# Phone_EE445L.net
KiCad netlist of a schematic drawn in EAGLE
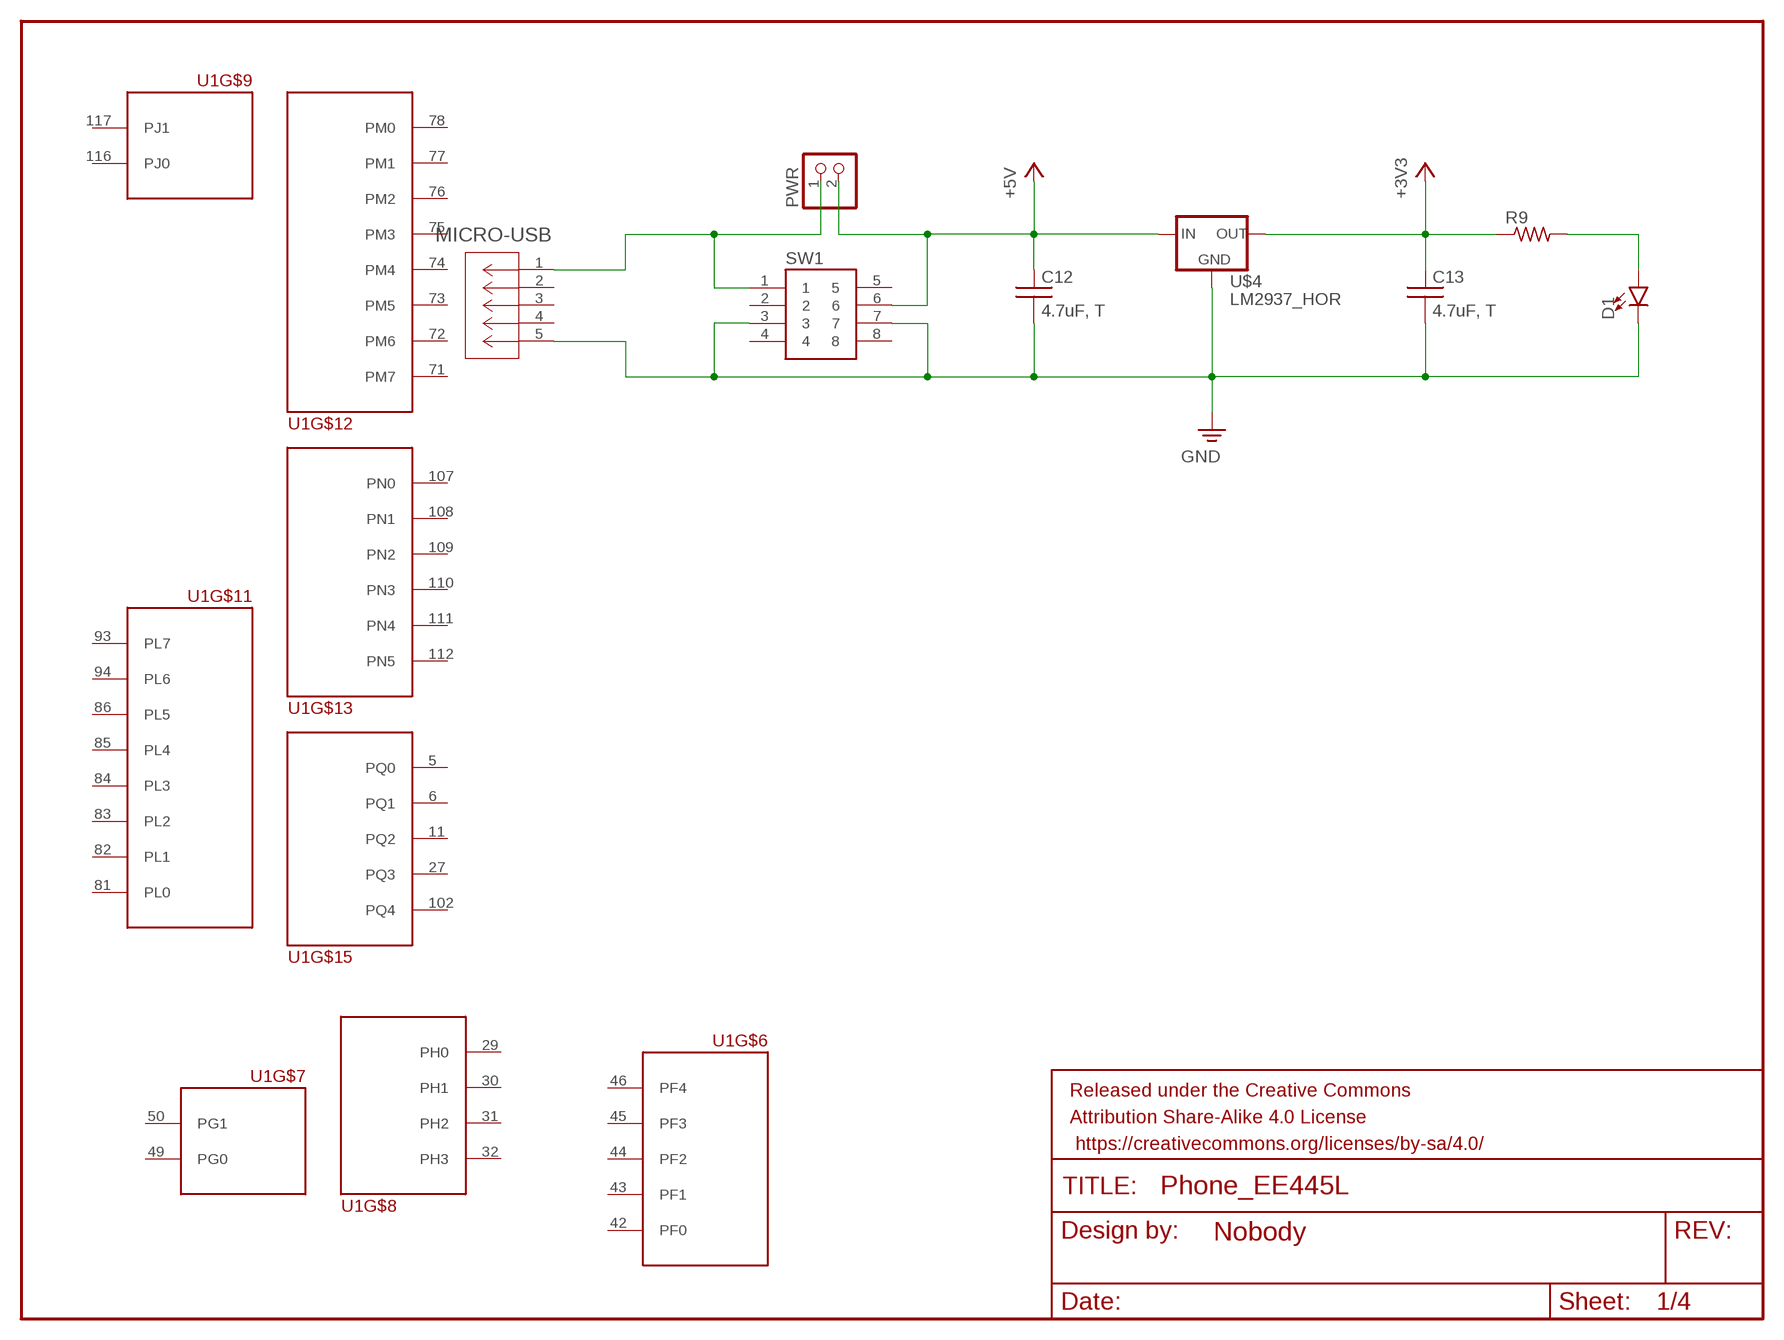
[diagram p0: schematic, sheet 1]
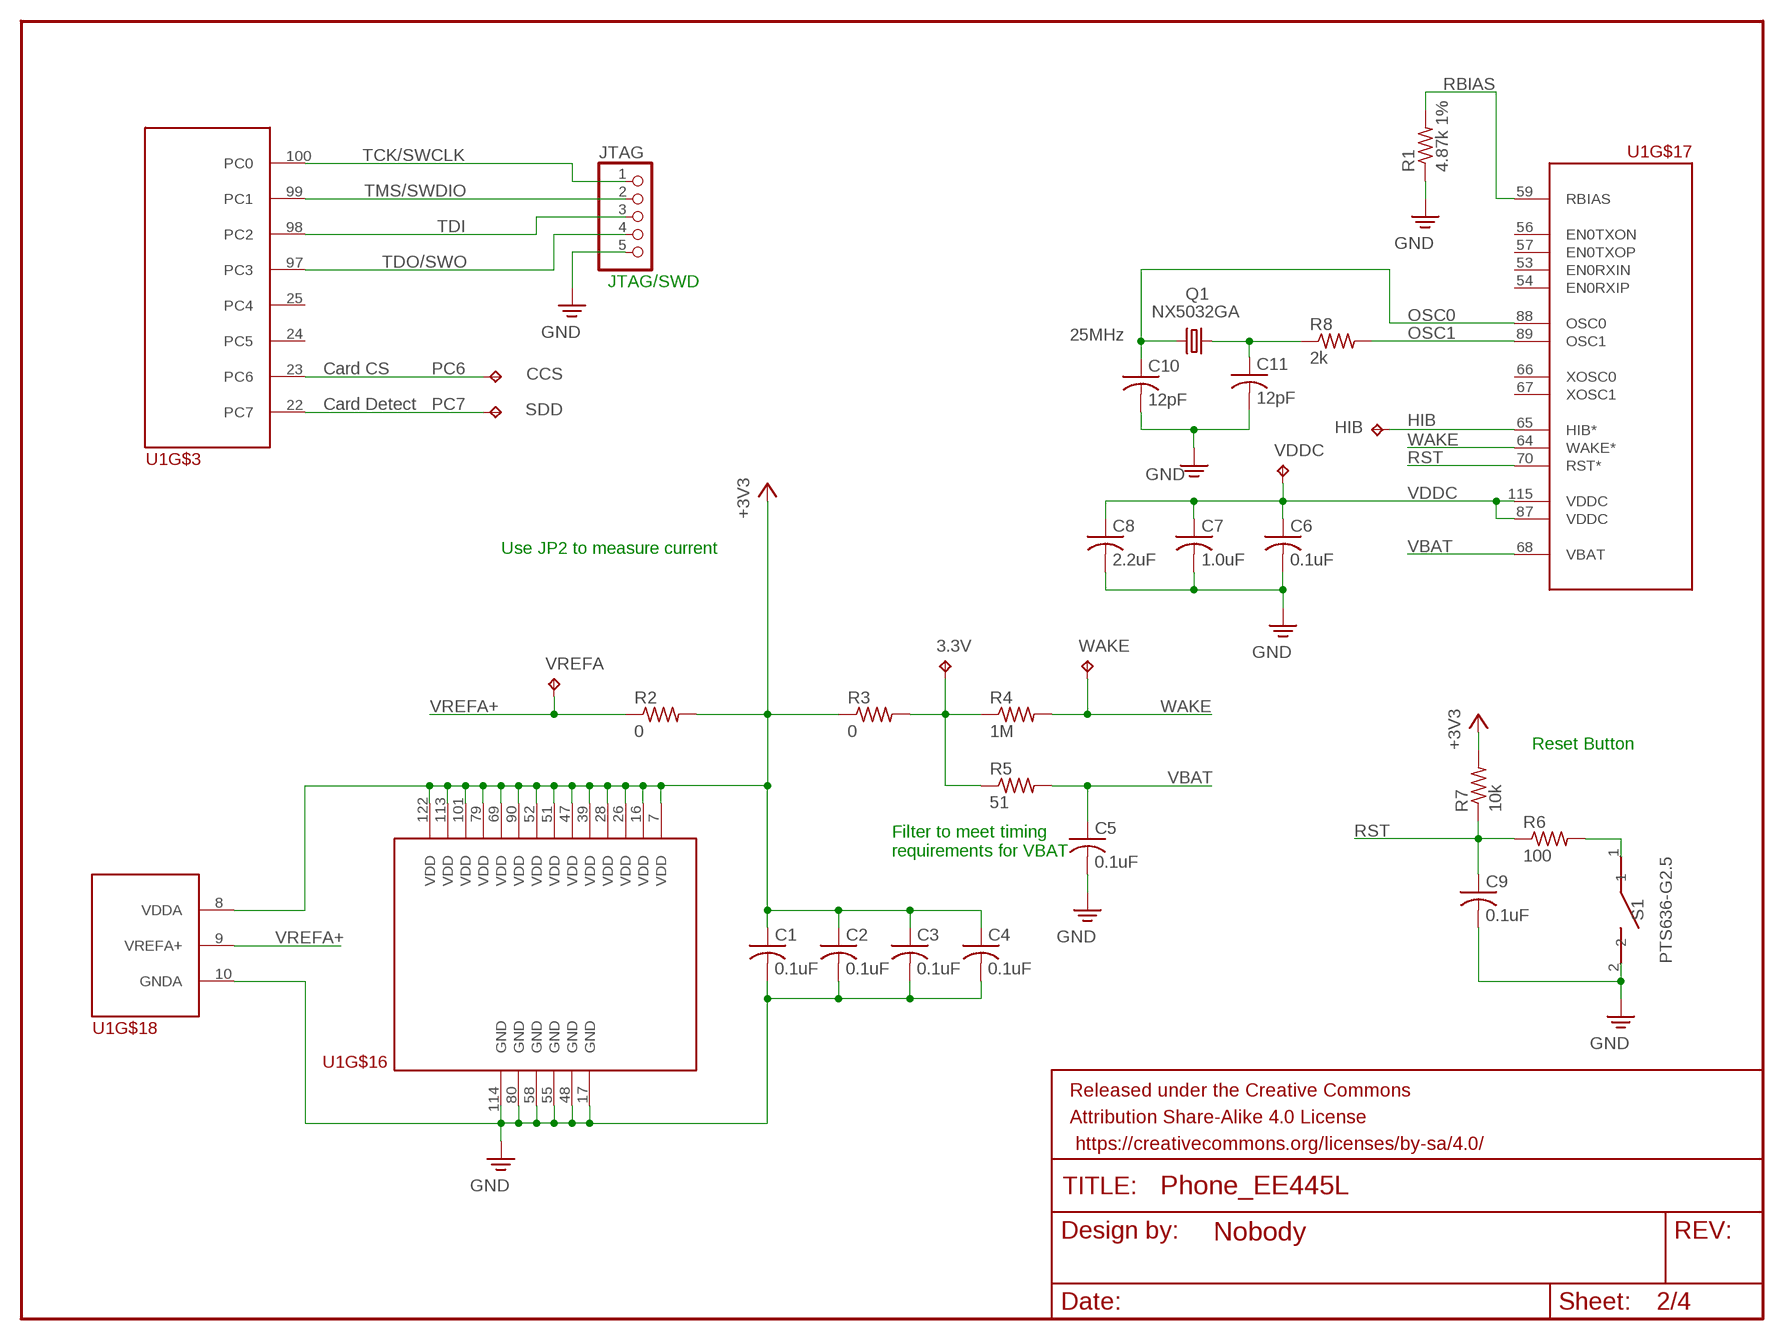
[diagram p1: schematic, sheet 2]
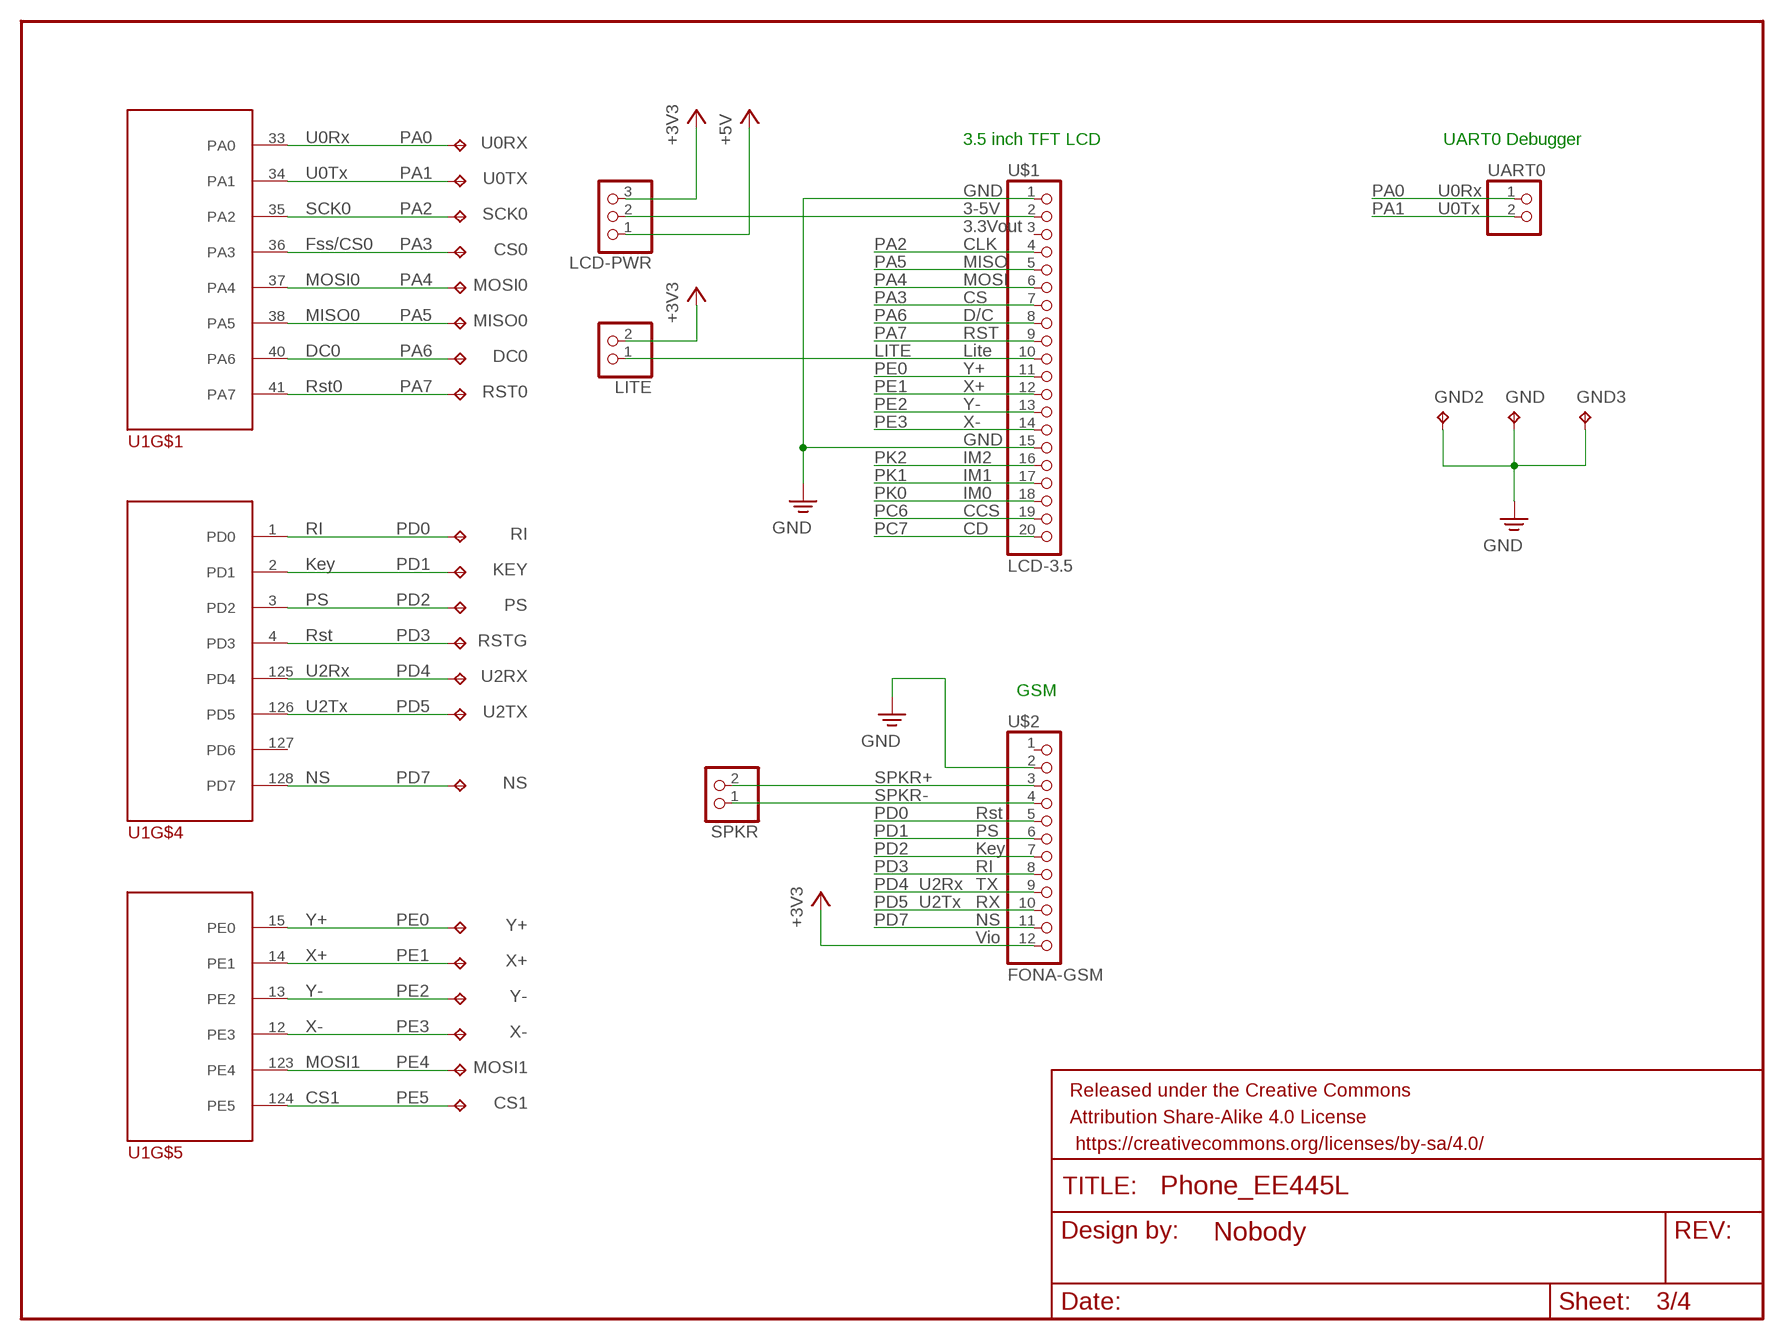
[diagram p2: schematic, sheet 3]
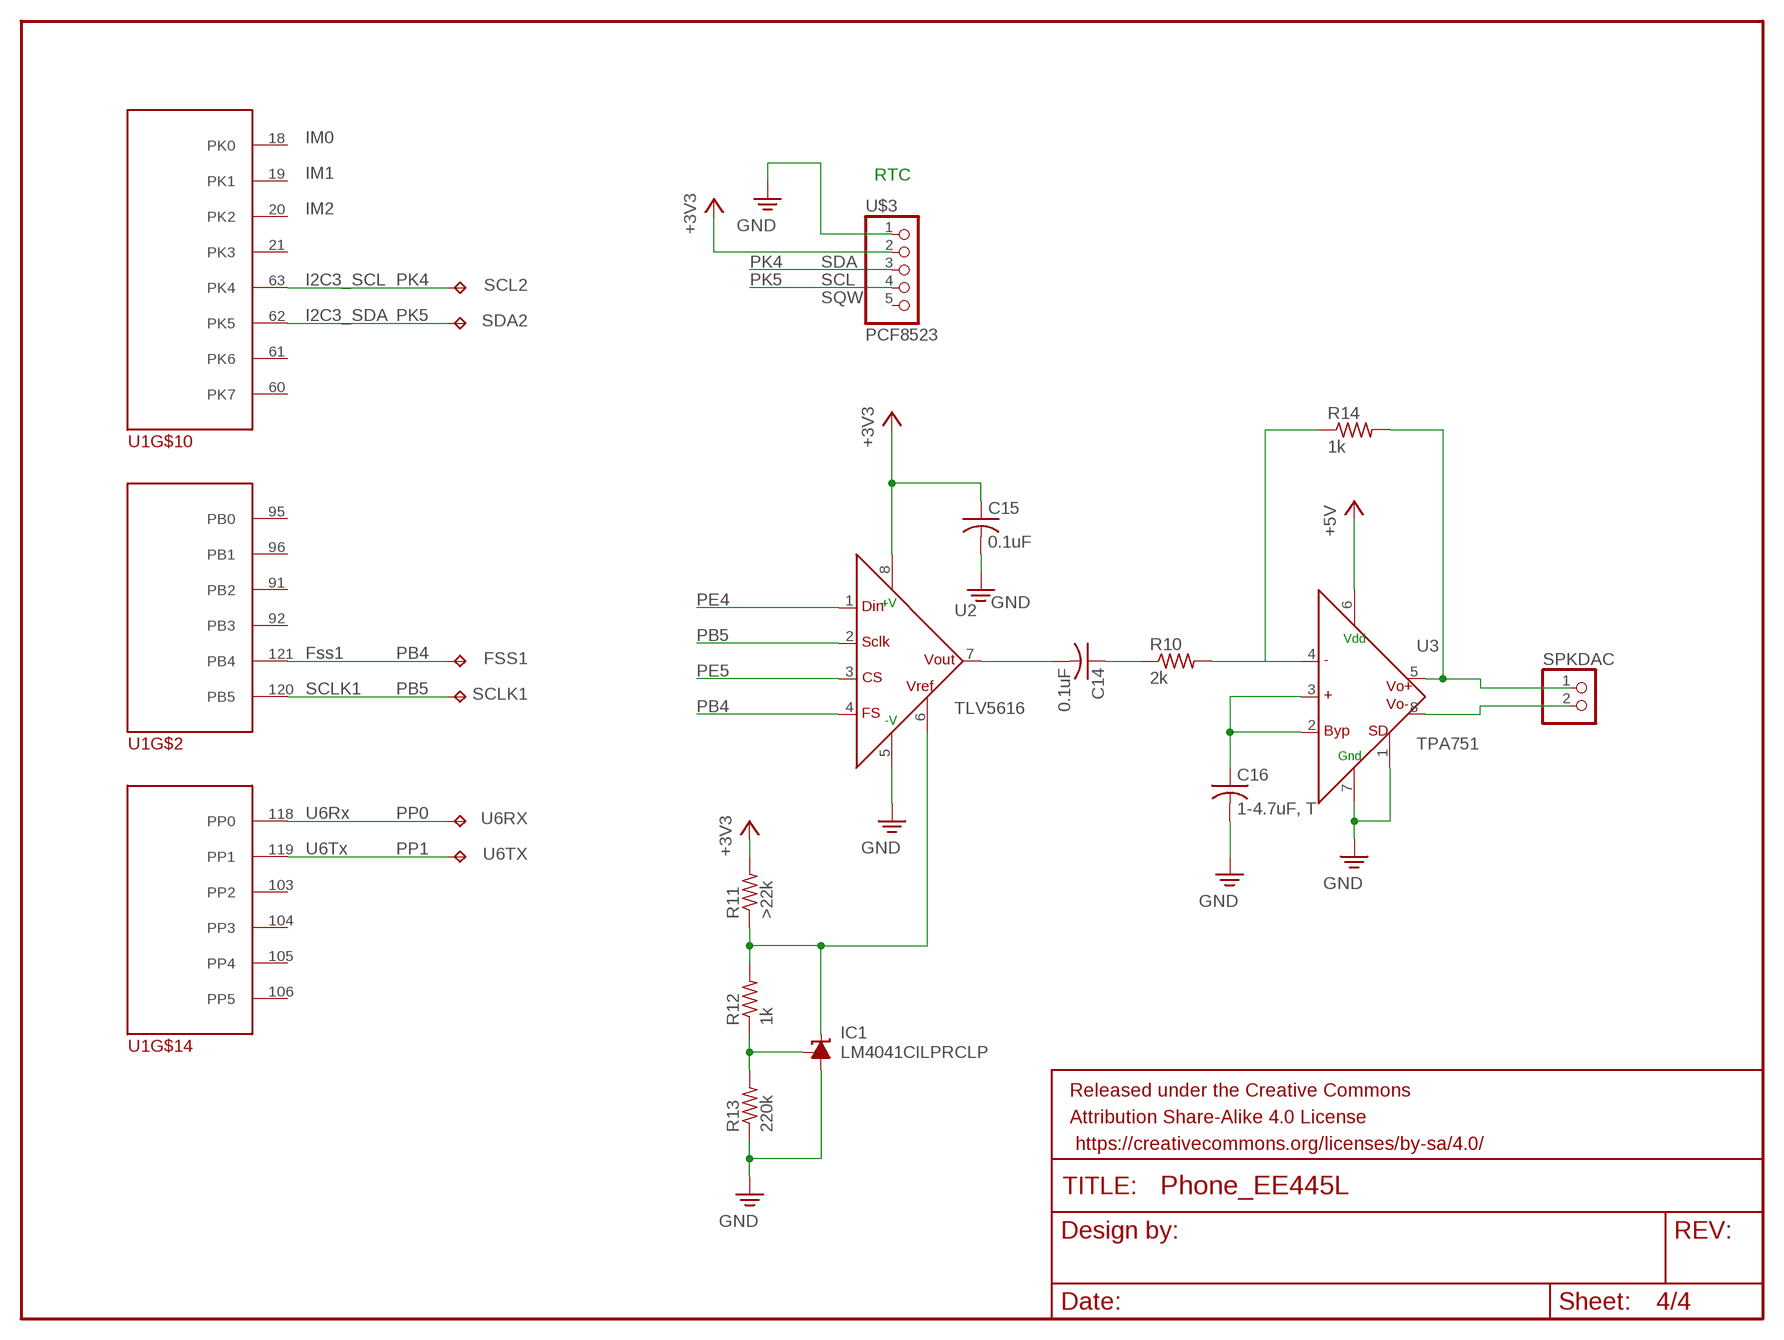
[diagram p3: schematic, sheet 4]

(export (version "E")
  (design (tool "Eeschema 10.0.6"))
  (components
    (comp (ref "C12")
      (value "4.7uF, T")
      (footprint "eagle-import:CAP200MIL")
      (libsource (lib "eagle-import") (part "CAPACITOR050-024X044"))
    )
    (comp (ref "C13")
      (value "4.7uF, T")
      (footprint "eagle-import:CAP200MIL")
      (libsource (lib "eagle-import") (part "CAPACITOR050-024X044"))
    )
    (comp (ref "D1")
      (value "LED0603")
      (footprint "eagle-import:LED-0603")
      (libsource (lib "eagle-import") (part "LED0603"))
    )
    (comp (ref "FRAME1")
      (value "FRAME-LETTERNO_PACKAGE")
      (footprint "eagle-import:DUMMY")
      (fields (field (name "DESIGNER") "Nobody"))
      (libsource (lib "eagle-import") (part "FRAME-LETTERNO_PACKAGE"))
    )
    (comp (ref "MICRO-USB")
      (value "ZX62D-B-5PA8(30)")
      (footprint "eagle-import:CONN5_ZX62D-B-5PA8")
      (fields (field (name "MANUFACTURER_PART_NUMBER") "ZX62DB5PA830"))
      (libsource (lib "eagle-import") (part "ZX62D-B-5PA8(30)"))
    )
    (comp (ref "PWR")
      (value "PINHD-1X2")
      (footprint "eagle-import:1X02")
      (libsource (lib "eagle-import") (part "PINHD-1X2"))
    )
    (comp (ref "R9")
      (value "R-US_R0805")
      (footprint "eagle-import:R0805")
      (libsource (lib "eagle-import") (part "R-US_R0805"))
    )
    (comp (ref "SW1")
      (value "PUSHBUTTON")
      (footprint "eagle-import:PWRBUTTON")
      (libsource (lib "eagle-import") (part "PUSHBUTTON"))
    )
    (comp (ref "U$4")
      (value "LM2937_HOR")
      (footprint "eagle-import:TO220")
      (libsource (lib "eagle-import") (part "LM2937_HOR"))
    )
    (comp (ref "U1")
      (value "TM4C129-MOD")
      (footprint "eagle-import:TQFP-128")
      (libsource (lib "eagle-import") (part "TM4C129-MOD"))
    )
    (comp (ref "3.3V")
      (value "TP_KEYSTONE500X")
      (footprint "eagle-import:P1.1MM")
      (libsource (lib "eagle-import") (part "TP_KEYSTONE500X"))
    )
    (comp (ref "C1")
      (value "0.1uF")
      (footprint "eagle-import:C0805")
      (libsource (lib "eagle-import") (part "C-USC0805"))
    )
    (comp (ref "C2")
      (value "0.1uF")
      (footprint "eagle-import:C0805")
      (libsource (lib "eagle-import") (part "C-USC0805"))
    )
    (comp (ref "C3")
      (value "0.1uF")
      (footprint "eagle-import:C0805")
      (libsource (lib "eagle-import") (part "C-USC0805"))
    )
    (comp (ref "C4")
      (value "0.1uF")
      (footprint "eagle-import:C0805")
      (libsource (lib "eagle-import") (part "C-USC0805"))
    )
    (comp (ref "C5")
      (value "0.1uF")
      (footprint "eagle-import:C0805")
      (libsource (lib "eagle-import") (part "C-USC0805"))
    )
    (comp (ref "C6")
      (value "0.1uF")
      (footprint "eagle-import:C0805")
      (libsource (lib "eagle-import") (part "C-USC0805"))
    )
    (comp (ref "C7")
      (value "1.0uF")
      (footprint "eagle-import:C0805")
      (libsource (lib "eagle-import") (part "C-USC0805"))
    )
    (comp (ref "C8")
      (value "2.2uF")
      (footprint "eagle-import:C0805")
      (libsource (lib "eagle-import") (part "C-USC0805"))
    )
    (comp (ref "C9")
      (value "0.1uF")
      (footprint "eagle-import:C0805")
      (libsource (lib "eagle-import") (part "C-USC0805"))
    )
    (comp (ref "C10")
      (value "12pF")
      (footprint "eagle-import:C0805")
      (libsource (lib "eagle-import") (part "C-USC0805"))
    )
    (comp (ref "C11")
      (value "12pF")
      (footprint "eagle-import:C0805")
      (libsource (lib "eagle-import") (part "C-USC0805"))
    )
    (comp (ref "CCS")
      (value "TP_KEYSTONE500X")
      (footprint "eagle-import:P1.1MM")
      (libsource (lib "eagle-import") (part "TP_KEYSTONE500X"))
    )
    (comp (ref "FRAME2")
      (value "FRAME-LETTERNO_PACKAGE")
      (footprint "eagle-import:DUMMY")
      (fields (field (name "DESIGNER") "Nobody"))
      (libsource (lib "eagle-import") (part "FRAME-LETTERNO_PACKAGE"))
    )
    (comp (ref "HIB")
      (value "TP_KEYSTONE500X")
      (footprint "eagle-import:P1.1MM")
      (libsource (lib "eagle-import") (part "TP_KEYSTONE500X"))
    )
    (comp (ref "JTAG")
      (value "PINHD-1X5")
      (footprint "eagle-import:1X05")
      (libsource (lib "eagle-import") (part "PINHD-1X5"))
    )
    (comp (ref "Q1")
      (value "NX5032GA")
      (footprint "eagle-import:NX5032GA")
      (libsource (lib "eagle-import") (part "NX5032GA"))
    )
    (comp (ref "R1")
      (value "4.87k 1%")
      (footprint "eagle-import:R0805")
      (libsource (lib "eagle-import") (part "R-US_R0805"))
    )
    (comp (ref "R2")
      (value "0")
      (footprint "eagle-import:R0805")
      (libsource (lib "eagle-import") (part "R-US_R0805"))
    )
    (comp (ref "R3")
      (value "0")
      (footprint "eagle-import:R0805")
      (libsource (lib "eagle-import") (part "R-US_R0805"))
    )
    (comp (ref "R4")
      (value "1M")
      (footprint "eagle-import:R0805")
      (libsource (lib "eagle-import") (part "R-US_R0805"))
    )
    (comp (ref "R5")
      (value "51")
      (footprint "eagle-import:R0805")
      (libsource (lib "eagle-import") (part "R-US_R0805"))
    )
    (comp (ref "R6")
      (value "100")
      (footprint "eagle-import:R0805")
      (libsource (lib "eagle-import") (part "R-US_R0805"))
    )
    (comp (ref "R7")
      (value "10k")
      (footprint "eagle-import:R0805")
      (libsource (lib "eagle-import") (part "R-US_R0805"))
    )
    (comp (ref "R8")
      (value "2k")
      (footprint "eagle-import:R0805")
      (libsource (lib "eagle-import") (part "R-US_R0805"))
    )
    (comp (ref "S1")
      (value "PTS636-G2.5")
      (footprint "eagle-import:PTS636-G")
      (libsource (lib "eagle-import") (part "PTS636-G2.5"))
    )
    (comp (ref "SDD")
      (value "TP_KEYSTONE500X")
      (footprint "eagle-import:P1.1MM")
      (libsource (lib "eagle-import") (part "TP_KEYSTONE500X"))
    )
    (comp (ref "VDDC")
      (value "TP_KEYSTONE500X")
      (footprint "eagle-import:P1.1MM")
      (libsource (lib "eagle-import") (part "TP_KEYSTONE500X"))
    )
    (comp (ref "VREFA")
      (value "TP_KEYSTONE500X")
      (footprint "eagle-import:P1.1MM")
      (libsource (lib "eagle-import") (part "TP_KEYSTONE500X"))
    )
    (comp (ref "WAKE")
      (value "TP_KEYSTONE500X")
      (footprint "eagle-import:P1.1MM")
      (libsource (lib "eagle-import") (part "TP_KEYSTONE500X"))
    )
    (comp (ref "CS0")
      (value "TP_KEYSTONE500X")
      (footprint "eagle-import:P1.1MM")
      (libsource (lib "eagle-import") (part "TP_KEYSTONE500X"))
    )
    (comp (ref "CS1")
      (value "TP_KEYSTONE500X")
      (footprint "eagle-import:P1.1MM")
      (libsource (lib "eagle-import") (part "TP_KEYSTONE500X"))
    )
    (comp (ref "DC0")
      (value "TP_KEYSTONE500X")
      (footprint "eagle-import:P1.1MM")
      (libsource (lib "eagle-import") (part "TP_KEYSTONE500X"))
    )
    (comp (ref "FRAME3")
      (value "FRAME-LETTERNO_PACKAGE")
      (footprint "eagle-import:DUMMY")
      (fields (field (name "DESIGNER") "Nobody"))
      (libsource (lib "eagle-import") (part "FRAME-LETTERNO_PACKAGE"))
    )
    (comp (ref "GND")
      (value "TP_KEYSTONE500X")
      (footprint "eagle-import:P1.1MM")
      (libsource (lib "eagle-import") (part "TP_KEYSTONE500X"))
    )
    (comp (ref "GND2")
      (value "TP_KEYSTONE500X")
      (footprint "eagle-import:P1.1MM")
      (libsource (lib "eagle-import") (part "TP_KEYSTONE500X"))
    )
    (comp (ref "GND3")
      (value "TP_KEYSTONE500X")
      (footprint "eagle-import:P1.1MM")
      (libsource (lib "eagle-import") (part "TP_KEYSTONE500X"))
    )
    (comp (ref "KEY")
      (value "TP_KEYSTONE500X")
      (footprint "eagle-import:P1.1MM")
      (libsource (lib "eagle-import") (part "TP_KEYSTONE500X"))
    )
    (comp (ref "LCD-PWR")
      (value "PINHD-1X3")
      (footprint "eagle-import:1X03")
      (libsource (lib "eagle-import") (part "PINHD-1X3"))
    )
    (comp (ref "LITE")
      (value "PINHD-1X2")
      (footprint "eagle-import:1X02")
      (libsource (lib "eagle-import") (part "PINHD-1X2"))
    )
    (comp (ref "MISO0")
      (value "TP_KEYSTONE500X")
      (footprint "eagle-import:P1.1MM")
      (libsource (lib "eagle-import") (part "TP_KEYSTONE500X"))
    )
    (comp (ref "MOSI0")
      (value "TP_KEYSTONE500X")
      (footprint "eagle-import:P1.1MM")
      (libsource (lib "eagle-import") (part "TP_KEYSTONE500X"))
    )
    (comp (ref "MOSI1")
      (value "TP_KEYSTONE500X")
      (footprint "eagle-import:P1.1MM")
      (libsource (lib "eagle-import") (part "TP_KEYSTONE500X"))
    )
    (comp (ref "NS")
      (value "TP_KEYSTONE500X")
      (footprint "eagle-import:P1.1MM")
      (libsource (lib "eagle-import") (part "TP_KEYSTONE500X"))
    )
    (comp (ref "PS")
      (value "TP_KEYSTONE500X")
      (footprint "eagle-import:P1.1MM")
      (libsource (lib "eagle-import") (part "TP_KEYSTONE500X"))
    )
    (comp (ref "RI")
      (value "TP_KEYSTONE500X")
      (footprint "eagle-import:P1.1MM")
      (libsource (lib "eagle-import") (part "TP_KEYSTONE500X"))
    )
    (comp (ref "RST0")
      (value "TP_KEYSTONE500X")
      (footprint "eagle-import:P1.1MM")
      (libsource (lib "eagle-import") (part "TP_KEYSTONE500X"))
    )
    (comp (ref "RSTG")
      (value "TP_KEYSTONE500X")
      (footprint "eagle-import:P1.1MM")
      (libsource (lib "eagle-import") (part "TP_KEYSTONE500X"))
    )
    (comp (ref "SCK0")
      (value "TP_KEYSTONE500X")
      (footprint "eagle-import:P1.1MM")
      (libsource (lib "eagle-import") (part "TP_KEYSTONE500X"))
    )
    (comp (ref "SPKR")
      (value "PINHD-1X2")
      (footprint "eagle-import:1X02")
      (libsource (lib "eagle-import") (part "PINHD-1X2"))
    )
    (comp (ref "U$1")
      (value "LCD-3.5")
      (footprint "eagle-import:LCD3.5IN")
      (libsource (lib "eagle-import") (part "LCD-3.5"))
    )
    (comp (ref "U$2")
      (value "FONA-GSM")
      (footprint "eagle-import:FONA")
      (libsource (lib "eagle-import") (part "FONA-GSM"))
    )
    (comp (ref "U0RX")
      (value "TP_KEYSTONE500X")
      (footprint "eagle-import:P1.1MM")
      (libsource (lib "eagle-import") (part "TP_KEYSTONE500X"))
    )
    (comp (ref "U0TX")
      (value "TP_KEYSTONE500X")
      (footprint "eagle-import:P1.1MM")
      (libsource (lib "eagle-import") (part "TP_KEYSTONE500X"))
    )
    (comp (ref "U2RX")
      (value "TP_KEYSTONE500X")
      (footprint "eagle-import:P1.1MM")
      (libsource (lib "eagle-import") (part "TP_KEYSTONE500X"))
    )
    (comp (ref "U2TX")
      (value "TP_KEYSTONE500X")
      (footprint "eagle-import:P1.1MM")
      (libsource (lib "eagle-import") (part "TP_KEYSTONE500X"))
    )
    (comp (ref "UART0")
      (value "PINHD-1X2")
      (footprint "eagle-import:1X02")
      (libsource (lib "eagle-import") (part "PINHD-1X2"))
    )
    (comp (ref "X+")
      (value "TP_KEYSTONE500X")
      (footprint "eagle-import:P1.1MM")
      (libsource (lib "eagle-import") (part "TP_KEYSTONE500X"))
    )
    (comp (ref "X-")
      (value "TP_KEYSTONE500X")
      (footprint "eagle-import:P1.1MM")
      (libsource (lib "eagle-import") (part "TP_KEYSTONE500X"))
    )
    (comp (ref "Y+")
      (value "TP_KEYSTONE500X")
      (footprint "eagle-import:P1.1MM")
      (libsource (lib "eagle-import") (part "TP_KEYSTONE500X"))
    )
    (comp (ref "Y-")
      (value "TP_KEYSTONE500X")
      (footprint "eagle-import:P1.1MM")
      (libsource (lib "eagle-import") (part "TP_KEYSTONE500X"))
    )
    (comp (ref "C14")
      (value "0.1uF")
      (footprint "eagle-import:C0805")
      (libsource (lib "eagle-import") (part "C-USC0805"))
    )
    (comp (ref "C15")
      (value "0.1uF")
      (footprint "eagle-import:C0805")
      (libsource (lib "eagle-import") (part "C-USC0805"))
    )
    (comp (ref "C16")
      (value "1-4.7uF, T")
      (footprint "eagle-import:C0805")
      (libsource (lib "eagle-import") (part "C-USC0805"))
    )
    (comp (ref "FRAME4")
      (value "FRAME-LETTERNO_PACKAGE")
      (footprint "eagle-import:DUMMY")
      (fields (field (name "DESIGNER") "Nobody"))
      (libsource (lib "eagle-import") (part "SparkFun-Aesthetics_507_FRAME-LETTERNO_PACKAGE"))
    )
    (comp (ref "FSS1")
      (value "TP_KEYSTONE500X")
      (footprint "eagle-import:P1.1MM")
      (libsource (lib "eagle-import") (part "TP_KEYSTONE500X"))
    )
    (comp (ref "IC1")
      (value "LM4041CILPRCLP")
      (footprint "eagle-import:LP_O-PBCY-W3")
      (fields (field (name "MPN") "LM4041CILP"))
      (libsource (lib "eagle-import") (part "LM4041CILPRLPC"))
    )
    (comp (ref "R10")
      (value "2k")
      (footprint "eagle-import:R0805")
      (libsource (lib "eagle-import") (part "R-US_R0805"))
    )
    (comp (ref "R11")
      (value ">22k")
      (footprint "eagle-import:R0805")
      (libsource (lib "eagle-import") (part "R-US_R0805"))
    )
    (comp (ref "R12")
      (value "1k")
      (footprint "eagle-import:R0805")
      (libsource (lib "eagle-import") (part "R-US_R0805"))
    )
    (comp (ref "R13")
      (value "220k")
      (footprint "eagle-import:R0805")
      (libsource (lib "eagle-import") (part "R-US_R0805"))
    )
    (comp (ref "R14")
      (value "1k")
      (footprint "eagle-import:R0805")
      (libsource (lib "eagle-import") (part "R-US_R0805"))
    )
    (comp (ref "SCL2")
      (value "TP_KEYSTONE500X")
      (footprint "eagle-import:P1.1MM")
      (libsource (lib "eagle-import") (part "TP_KEYSTONE500X"))
    )
    (comp (ref "SCLK1")
      (value "TP_KEYSTONE500X")
      (footprint "eagle-import:P1.1MM")
      (libsource (lib "eagle-import") (part "TP_KEYSTONE500X"))
    )
    (comp (ref "SDA2")
      (value "TP_KEYSTONE500X")
      (footprint "eagle-import:P1.1MM")
      (libsource (lib "eagle-import") (part "TP_KEYSTONE500X"))
    )
    (comp (ref "SPKDAC")
      (value "PINHD-1X2")
      (footprint "eagle-import:1X02")
      (libsource (lib "eagle-import") (part "PINHD-1X2"))
    )
    (comp (ref "U$3")
      (value "PCF8523")
      (footprint "eagle-import:PCF8523")
      (libsource (lib "eagle-import") (part "PCF8523"))
    )
    (comp (ref "U2")
      (value "TLV5616")
      (footprint "eagle-import:DIL08")
      (libsource (lib "eagle-import") (part "TLV5616"))
    )
    (comp (ref "U3")
      (value "TPA751")
      (footprint "eagle-import:SO08")
      (libsource (lib "eagle-import") (part "TPA751"))
    )
    (comp (ref "U6RX")
      (value "TP_KEYSTONE500X")
      (footprint "eagle-import:P1.1MM")
      (libsource (lib "eagle-import") (part "TP_KEYSTONE500X"))
    )
    (comp (ref "U6TX")
      (value "TP_KEYSTONE500X")
      (footprint "eagle-import:P1.1MM")
      (libsource (lib "eagle-import") (part "TP_KEYSTONE500X"))
    )
  )
  (nets
    (net (code "1") (name "+3V3") (class "Default")
      (node (ref "C1") (pin "1") (pinfunction "1_1") (pintype "passive"))
      (node (ref "C13") (pin "1") (pinfunction "1_1") (pintype "passive"))
      (node (ref "C15") (pin "1") (pinfunction "1_1") (pintype "passive"))
      (node (ref "C2") (pin "1") (pinfunction "1_1") (pintype "passive"))
      (node (ref "C3") (pin "1") (pinfunction "1_1") (pintype "passive"))
      (node (ref "C4") (pin "1") (pinfunction "1_1") (pintype "passive"))
      (node (ref "LCD-PWR") (pin "3") (pinfunction "3_3") (pintype "passive"))
      (node (ref "LITE") (pin "2") (pinfunction "2_2") (pintype "passive"))
      (node (ref "R11") (pin "2") (pinfunction "2_2") (pintype "passive"))
      (node (ref "R2") (pin "2") (pinfunction "2_2") (pintype "passive"))
      (node (ref "R3") (pin "1") (pinfunction "1_1") (pintype "passive"))
      (node (ref "R7") (pin "2") (pinfunction "2_2") (pintype "passive"))
      (node (ref "R9") (pin "1") (pinfunction "1_1") (pintype "passive"))
      (node (ref "U$2") (pin "12") (pinfunction "12_12") (pintype "passive"))
      (node (ref "U$3") (pin "2") (pinfunction "2_2") (pintype "passive"))
      (node (ref "U$4") (pin "3") (pinfunction "OUT_3") (pintype "passive"))
      (node (ref "U1") (pin "101") (pinfunction "VDD_101") (pintype "power_in"))
      (node (ref "U1") (pin "113") (pinfunction "VDD_113") (pintype "power_in"))
      (node (ref "U1") (pin "122") (pinfunction "VDD_122") (pintype "power_in"))
      (node (ref "U1") (pin "16") (pinfunction "VDD_16") (pintype "power_in"))
      (node (ref "U1") (pin "26") (pinfunction "VDD_26") (pintype "power_in"))
      (node (ref "U1") (pin "28") (pinfunction "VDD_28") (pintype "power_in"))
      (node (ref "U1") (pin "39") (pinfunction "VDD_39") (pintype "power_in"))
      (node (ref "U1") (pin "47") (pinfunction "VDD_47") (pintype "power_in"))
      (node (ref "U1") (pin "51") (pinfunction "VDD_51") (pintype "power_in"))
      (node (ref "U1") (pin "52") (pinfunction "VDD_52") (pintype "power_in"))
      (node (ref "U1") (pin "69") (pinfunction "VDD_69") (pintype "power_in"))
      (node (ref "U1") (pin "7") (pinfunction "VDD_7") (pintype "power_in"))
      (node (ref "U1") (pin "79") (pinfunction "VDD_79") (pintype "power_in"))
      (node (ref "U1") (pin "8") (pinfunction "VDDA_8") (pintype "power_in"))
      (node (ref "U1") (pin "90") (pinfunction "VDD_90") (pintype "power_in"))
      (node (ref "U2") (pin "8") (pinfunction "VDD_8") (pintype "power_in"))
    )
    (net (code "2") (name "+5V") (class "Default")
      (node (ref "C12") (pin "1") (pinfunction "1_1") (pintype "passive"))
      (node (ref "LCD-PWR") (pin "1") (pinfunction "1_1") (pintype "passive"))
      (node (ref "PWR") (pin "2") (pinfunction "2_2") (pintype "passive"))
      (node (ref "SW1") (pin "6") (pinfunction "6_6") (pintype "output"))
      (node (ref "U$4") (pin "1") (pinfunction "IN_1") (pintype "input"))
      (node (ref "U3") (pin "6") (pinfunction "VDD_6") (pintype "power_in"))
    )
    (net (code "3") (name "GND") (class "Default")
      (node (ref "C1") (pin "2") (pinfunction "2_2") (pintype "passive"))
      (node (ref "C10") (pin "2") (pinfunction "2_2") (pintype "passive"))
      (node (ref "C11") (pin "2") (pinfunction "2_2") (pintype "passive"))
      (node (ref "C12") (pin "2") (pinfunction "2_2") (pintype "passive"))
      (node (ref "C13") (pin "2") (pinfunction "2_2") (pintype "passive"))
      (node (ref "C15") (pin "2") (pinfunction "2_2") (pintype "passive"))
      (node (ref "C16") (pin "2") (pinfunction "2_2") (pintype "passive"))
      (node (ref "C2") (pin "2") (pinfunction "2_2") (pintype "passive"))
      (node (ref "C3") (pin "2") (pinfunction "2_2") (pintype "passive"))
      (node (ref "C4") (pin "2") (pinfunction "2_2") (pintype "passive"))
      (node (ref "C5") (pin "2") (pinfunction "2_2") (pintype "passive"))
      (node (ref "C6") (pin "2") (pinfunction "2_2") (pintype "passive"))
      (node (ref "C7") (pin "2") (pinfunction "2_2") (pintype "passive"))
      (node (ref "C8") (pin "2") (pinfunction "2_2") (pintype "passive"))
      (node (ref "C9") (pin "2") (pinfunction "2_2") (pintype "passive"))
      (node (ref "D1") (pin "C") (pinfunction "C_C") (pintype "passive"))
      (node (ref "GND") (pin "TP") (pinfunction "TP_TP") (pintype "input"))
      (node (ref "GND2") (pin "TP") (pinfunction "TP_TP") (pintype "input"))
      (node (ref "GND3") (pin "TP") (pinfunction "TP_TP") (pintype "input"))
      (node (ref "IC1") (pin "3") (pinfunction "A_3") (pintype "passive"))
      (node (ref "JTAG") (pin "5") (pinfunction "5_5") (pintype "passive"))
      (node (ref "MICRO-USB") (pin "5") (pinfunction "5_5") (pintype "passive"))
      (node (ref "R1") (pin "1") (pinfunction "1_1") (pintype "passive"))
      (node (ref "R13") (pin "1") (pinfunction "1_1") (pintype "passive"))
      (node (ref "S1") (pin "2") (pinfunction "2_2") (pintype "bidirectional"))
      (node (ref "SW1") (pin "3") (pinfunction "3_3") (pintype "power_in"))
      (node (ref "SW1") (pin "7") (pinfunction "7_7") (pintype "power_in"))
      (node (ref "U$1") (pin "1") (pinfunction "1_1") (pintype "passive"))
      (node (ref "U$1") (pin "15") (pinfunction "15_15") (pintype "passive"))
      (node (ref "U$2") (pin "2") (pinfunction "2_2") (pintype "passive"))
      (node (ref "U$3") (pin "1") (pinfunction "1_1") (pintype "passive"))
      (node (ref "U$4") (pin "2") (pinfunction "GND_2") (pintype "input"))
      (node (ref "U1") (pin "10") (pinfunction "GNDA_10") (pintype "power_in"))
      (node (ref "U1") (pin "114") (pinfunction "GND_114") (pintype "power_in"))
      (node (ref "U1") (pin "17") (pinfunction "GND_17") (pintype "power_in"))
      (node (ref "U1") (pin "48") (pinfunction "GND_48") (pintype "power_in"))
      (node (ref "U1") (pin "55") (pinfunction "GND_55") (pintype "power_in"))
      (node (ref "U1") (pin "58") (pinfunction "GND_58") (pintype "power_in"))
      (node (ref "U1") (pin "80") (pinfunction "GND_80") (pintype "power_in"))
      (node (ref "U2") (pin "5") (pinfunction "AGND_5") (pintype "power_in"))
      (node (ref "U3") (pin "1") (pinfunction "SHUTDOWN_1") (pintype "passive"))
      (node (ref "U3") (pin "7") (pinfunction "GND_7") (pintype "power_in"))
    )
    (net (code "4") (name "HIB") (class "Default")
      (node (ref "HIB") (pin "TP") (pinfunction "TP_TP") (pintype "input"))
      (node (ref "U1") (pin "65") (pinfunction "HIB*_65") (pintype "input"))
    )
    (net (code "5") (name "LITE") (class "Default")
      (node (ref "LITE") (pin "1") (pinfunction "1_1") (pintype "passive"))
      (node (ref "U$1") (pin "10") (pinfunction "10_10") (pintype "passive"))
    )
    (net (code "6") (name "Net-(3.3V-PadTP)") (class "Default")
      (node (ref "3.3V") (pin "TP") (pinfunction "TP_TP") (pintype "input"))
      (node (ref "R3") (pin "2") (pinfunction "2_2") (pintype "passive"))
      (node (ref "R4") (pin "1") (pinfunction "1_1") (pintype "passive"))
      (node (ref "R5") (pin "1") (pinfunction "1_1") (pintype "passive"))
    )
    (net (code "7") (name "Net-(C11-Pad1)") (class "Default")
      (node (ref "C11") (pin "1") (pinfunction "1_1") (pintype "passive"))
      (node (ref "Q1") (pin "1") (pinfunction "1_1") (pintype "passive"))
      (node (ref "R8") (pin "1") (pinfunction "1_1") (pintype "passive"))
    )
    (net (code "8") (name "Net-(C14-Pad1)") (class "Default")
      (node (ref "C14") (pin "1") (pinfunction "1_1") (pintype "passive"))
      (node (ref "R10") (pin "1") (pinfunction "1_1") (pintype "passive"))
    )
    (net (code "9") (name "Net-(D1-PadA)") (class "Default")
      (node (ref "D1") (pin "A") (pinfunction "A_A") (pintype "passive"))
      (node (ref "R9") (pin "2") (pinfunction "2_2") (pintype "passive"))
    )
    (net (code "10") (name "Net-(IC1-C)") (class "Default")
      (node (ref "IC1") (pin "2") (pinfunction "C_2") (pintype "passive"))
      (node (ref "R11") (pin "1") (pinfunction "1_1") (pintype "passive"))
      (node (ref "R12") (pin "2") (pinfunction "2_2") (pintype "passive"))
      (node (ref "U2") (pin "6") (pinfunction "REFIN_6") (pintype "passive"))
    )
    (net (code "11") (name "Net-(IC1-FB)") (class "Default")
      (node (ref "IC1") (pin "1") (pinfunction "FB_1") (pintype "passive"))
      (node (ref "R12") (pin "1") (pinfunction "1_1") (pintype "passive"))
      (node (ref "R13") (pin "2") (pinfunction "2_2") (pintype "passive"))
    )
    (net (code "12") (name "Net-(LCD-PWR-Pad2)") (class "Default")
      (node (ref "LCD-PWR") (pin "2") (pinfunction "2_2") (pintype "passive"))
      (node (ref "U$1") (pin "2") (pinfunction "2_2") (pintype "passive"))
    )
    (net (code "13") (name "Net-(MICRO-USB-Pad1)") (class "Default")
      (node (ref "MICRO-USB") (pin "1") (pinfunction "1_1") (pintype "passive"))
      (node (ref "PWR") (pin "1") (pinfunction "1_1") (pintype "passive"))
      (node (ref "SW1") (pin "1") (pinfunction "1_1") (pintype "input"))
    )
    (net (code "14") (name "Net-(R6-Pad2)") (class "Default")
      (node (ref "R6") (pin "2") (pinfunction "2_2") (pintype "passive"))
      (node (ref "S1") (pin "1") (pinfunction "1_1") (pintype "bidirectional"))
    )
    (net (code "15") (name "Net-(U2-OUT)") (class "Default")
      (node (ref "C14") (pin "2") (pinfunction "2_2") (pintype "passive"))
      (node (ref "U2") (pin "7") (pinfunction "OUT_7") (pintype "output"))
    )
    (net (code "16") (name "Net-(U3-BYPASS)") (class "Default")
      (node (ref "C16") (pin "1") (pinfunction "1_1") (pintype "passive"))
      (node (ref "U3") (pin "2") (pinfunction "BYPASS_2") (pintype "input"))
      (node (ref "U3") (pin "3") (pinfunction "IN+_3") (pintype "passive"))
    )
    (net (code "17") (name "Net-(U3-IN-)") (class "Default")
      (node (ref "R10") (pin "2") (pinfunction "2_2") (pintype "passive"))
      (node (ref "R14") (pin "1") (pinfunction "1_1") (pintype "passive"))
      (node (ref "U3") (pin "4") (pinfunction "IN-_4") (pintype "passive"))
    )
    (net (code "18") (name "Net-(U3-VO+)") (class "Default")
      (node (ref "R14") (pin "2") (pinfunction "2_2") (pintype "passive"))
      (node (ref "SPKDAC") (pin "1") (pinfunction "1_1") (pintype "passive"))
      (node (ref "U3") (pin "5") (pinfunction "VO+_5") (pintype "output"))
    )
    (net (code "19") (name "Net-(U3-VO-)") (class "Default")
      (node (ref "SPKDAC") (pin "2") (pinfunction "2_2") (pintype "passive"))
      (node (ref "U3") (pin "8") (pinfunction "VO-_8") (pintype "output"))
    )
    (net (code "20") (name "OSC0") (class "Default")
      (node (ref "C10") (pin "1") (pinfunction "1_1") (pintype "passive"))
      (node (ref "Q1") (pin "2") (pinfunction "2_2") (pintype "passive"))
      (node (ref "U1") (pin "88") (pinfunction "OSC0_88") (pintype "bidirectional"))
    )
    (net (code "21") (name "OSC1") (class "Default")
      (node (ref "R8") (pin "2") (pinfunction "2_2") (pintype "passive"))
      (node (ref "U1") (pin "89") (pinfunction "OSC1_89") (pintype "bidirectional"))
    )
    (net (code "22") (name "PA0") (class "Default")
      (node (ref "U0RX") (pin "TP") (pinfunction "TP_TP") (pintype "input"))
      (node (ref "U1") (pin "33") (pinfunction "PA0_33") (pintype "bidirectional"))
      (node (ref "UART0") (pin "1") (pinfunction "1_1") (pintype "passive"))
    )
    (net (code "23") (name "PA1") (class "Default")
      (node (ref "U0TX") (pin "TP") (pinfunction "TP_TP") (pintype "input"))
      (node (ref "U1") (pin "34") (pinfunction "PA1_34") (pintype "bidirectional"))
      (node (ref "UART0") (pin "2") (pinfunction "2_2") (pintype "passive"))
    )
    (net (code "24") (name "PA2") (class "Default")
      (node (ref "SCK0") (pin "TP") (pinfunction "TP_TP") (pintype "input"))
      (node (ref "U$1") (pin "4") (pinfunction "4_4") (pintype "passive"))
      (node (ref "U1") (pin "35") (pinfunction "PA2_35") (pintype "bidirectional"))
    )
    (net (code "25") (name "PA3") (class "Default")
      (node (ref "CS0") (pin "TP") (pinfunction "TP_TP") (pintype "input"))
      (node (ref "U$1") (pin "7") (pinfunction "7_7") (pintype "passive"))
      (node (ref "U1") (pin "36") (pinfunction "PA3_36") (pintype "bidirectional"))
    )
    (net (code "26") (name "PA4") (class "Default")
      (node (ref "MOSI0") (pin "TP") (pinfunction "TP_TP") (pintype "input"))
      (node (ref "U$1") (pin "6") (pinfunction "6_6") (pintype "passive"))
      (node (ref "U1") (pin "37") (pinfunction "PA4_37") (pintype "bidirectional"))
    )
    (net (code "27") (name "PA5") (class "Default")
      (node (ref "MISO0") (pin "TP") (pinfunction "TP_TP") (pintype "input"))
      (node (ref "U$1") (pin "5") (pinfunction "5_5") (pintype "passive"))
      (node (ref "U1") (pin "38") (pinfunction "PA5_38") (pintype "bidirectional"))
    )
    (net (code "28") (name "PA6") (class "Default")
      (node (ref "DC0") (pin "TP") (pinfunction "TP_TP") (pintype "input"))
      (node (ref "U$1") (pin "8") (pinfunction "8_8") (pintype "passive"))
      (node (ref "U1") (pin "40") (pinfunction "PA6_40") (pintype "bidirectional"))
    )
    (net (code "29") (name "PA7") (class "Default")
      (node (ref "RST0") (pin "TP") (pinfunction "TP_TP") (pintype "input"))
      (node (ref "U$1") (pin "9") (pinfunction "9_9") (pintype "passive"))
      (node (ref "U1") (pin "41") (pinfunction "PA7_41") (pintype "bidirectional"))
    )
    (net (code "30") (name "PB4") (class "Default")
      (node (ref "FSS1") (pin "TP") (pinfunction "TP_TP") (pintype "input"))
      (node (ref "U1") (pin "121") (pinfunction "PB4_121") (pintype "bidirectional"))
      (node (ref "U2") (pin "4") (pinfunction "FS_4") (pintype "input"))
    )
    (net (code "31") (name "PB5") (class "Default")
      (node (ref "SCLK1") (pin "TP") (pinfunction "TP_TP") (pintype "input"))
      (node (ref "U1") (pin "120") (pinfunction "PB5_120") (pintype "bidirectional"))
      (node (ref "U2") (pin "2") (pinfunction "SCLK_2") (pintype "input"))
    )
    (net (code "32") (name "PC6") (class "Default")
      (node (ref "CCS") (pin "TP") (pinfunction "TP_TP") (pintype "input"))
      (node (ref "U$1") (pin "19") (pinfunction "19_19") (pintype "passive"))
      (node (ref "U1") (pin "23") (pinfunction "PC6_23") (pintype "bidirectional"))
    )
    (net (code "33") (name "PC7") (class "Default")
      (node (ref "SDD") (pin "TP") (pinfunction "TP_TP") (pintype "input"))
      (node (ref "U$1") (pin "20") (pinfunction "20_20") (pintype "passive"))
      (node (ref "U1") (pin "22") (pinfunction "PC7_22") (pintype "bidirectional"))
    )
    (net (code "34") (name "PD0") (class "Default")
      (node (ref "RI") (pin "TP") (pinfunction "TP_TP") (pintype "input"))
      (node (ref "U$2") (pin "5") (pinfunction "5_5") (pintype "passive"))
      (node (ref "U1") (pin "1") (pinfunction "PD0_1") (pintype "bidirectional"))
    )
    (net (code "35") (name "PD1") (class "Default")
      (node (ref "KEY") (pin "TP") (pinfunction "TP_TP") (pintype "input"))
      (node (ref "U$2") (pin "6") (pinfunction "6_6") (pintype "passive"))
      (node (ref "U1") (pin "2") (pinfunction "PD1_2") (pintype "bidirectional"))
    )
    (net (code "36") (name "PD2") (class "Default")
      (node (ref "PS") (pin "TP") (pinfunction "TP_TP") (pintype "input"))
      (node (ref "U$2") (pin "7") (pinfunction "7_7") (pintype "passive"))
      (node (ref "U1") (pin "3") (pinfunction "PD2_3") (pintype "bidirectional"))
    )
    (net (code "37") (name "PD3") (class "Default")
      (node (ref "RSTG") (pin "TP") (pinfunction "TP_TP") (pintype "input"))
      (node (ref "U$2") (pin "8") (pinfunction "8_8") (pintype "passive"))
      (node (ref "U1") (pin "4") (pinfunction "PD3_4") (pintype "bidirectional"))
    )
    (net (code "38") (name "PD4") (class "Default")
      (node (ref "U$2") (pin "9") (pinfunction "9_9") (pintype "passive"))
      (node (ref "U1") (pin "125") (pinfunction "PD4_125") (pintype "bidirectional"))
      (node (ref "U2RX") (pin "TP") (pinfunction "TP_TP") (pintype "input"))
    )
    (net (code "39") (name "PD5") (class "Default")
      (node (ref "U$2") (pin "10") (pinfunction "10_10") (pintype "passive"))
      (node (ref "U1") (pin "126") (pinfunction "PD5_126") (pintype "bidirectional"))
      (node (ref "U2TX") (pin "TP") (pinfunction "TP_TP") (pintype "input"))
    )
    (net (code "40") (name "PD7") (class "Default")
      (node (ref "NS") (pin "TP") (pinfunction "TP_TP") (pintype "input"))
      (node (ref "U$2") (pin "11") (pinfunction "11_11") (pintype "passive"))
      (node (ref "U1") (pin "128") (pinfunction "PD7_128") (pintype "bidirectional"))
    )
    (net (code "41") (name "PE0") (class "Default")
      (node (ref "U$1") (pin "11") (pinfunction "11_11") (pintype "passive"))
      (node (ref "U1") (pin "15") (pinfunction "PE0_15") (pintype "bidirectional"))
      (node (ref "Y+") (pin "TP") (pinfunction "TP_TP") (pintype "input"))
    )
    (net (code "42") (name "PE1") (class "Default")
      (node (ref "U$1") (pin "12") (pinfunction "12_12") (pintype "passive"))
      (node (ref "U1") (pin "14") (pinfunction "PE1_14") (pintype "bidirectional"))
      (node (ref "X+") (pin "TP") (pinfunction "TP_TP") (pintype "input"))
    )
    (net (code "43") (name "PE2") (class "Default")
      (node (ref "U$1") (pin "13") (pinfunction "13_13") (pintype "passive"))
      (node (ref "U1") (pin "13") (pinfunction "PE2_13") (pintype "bidirectional"))
      (node (ref "Y-") (pin "TP") (pinfunction "TP_TP") (pintype "input"))
    )
    (net (code "44") (name "PE3") (class "Default")
      (node (ref "U$1") (pin "14") (pinfunction "14_14") (pintype "passive"))
      (node (ref "U1") (pin "12") (pinfunction "PE3_12") (pintype "bidirectional"))
      (node (ref "X-") (pin "TP") (pinfunction "TP_TP") (pintype "input"))
    )
    (net (code "45") (name "PE4") (class "Default")
      (node (ref "MOSI1") (pin "TP") (pinfunction "TP_TP") (pintype "input"))
      (node (ref "U1") (pin "123") (pinfunction "PE4_123") (pintype "bidirectional"))
      (node (ref "U2") (pin "1") (pinfunction "DIN_1") (pintype "input"))
    )
    (net (code "46") (name "PE5") (class "Default")
      (node (ref "CS1") (pin "TP") (pinfunction "TP_TP") (pintype "input"))
      (node (ref "U1") (pin "124") (pinfunction "PE5_124") (pintype "bidirectional"))
      (node (ref "U2") (pin "3") (pinfunction "CS_3") (pintype "input"))
    )
    (net (code "47") (name "PK0") (class "Default")
      (node (ref "U$1") (pin "18") (pinfunction "18_18") (pintype "passive"))
    )
    (net (code "48") (name "PK1") (class "Default")
      (node (ref "U$1") (pin "17") (pinfunction "17_17") (pintype "passive"))
    )
    (net (code "49") (name "PK2") (class "Default")
      (node (ref "U$1") (pin "16") (pinfunction "16_16") (pintype "passive"))
    )
    (net (code "50") (name "PK4") (class "Default")
      (node (ref "SCL2") (pin "TP") (pinfunction "TP_TP") (pintype "input"))
      (node (ref "U$3") (pin "3") (pinfunction "3_3") (pintype "passive"))
      (node (ref "U1") (pin "63") (pinfunction "PK4_63") (pintype "bidirectional"))
    )
    (net (code "51") (name "PK5") (class "Default")
      (node (ref "SDA2") (pin "TP") (pinfunction "TP_TP") (pintype "input"))
      (node (ref "U$3") (pin "4") (pinfunction "4_4") (pintype "passive"))
      (node (ref "U1") (pin "62") (pinfunction "PK5_62") (pintype "bidirectional"))
    )
    (net (code "52") (name "PP0") (class "Default")
      (node (ref "U1") (pin "118") (pinfunction "PP0_118") (pintype "bidirectional"))
      (node (ref "U6RX") (pin "TP") (pinfunction "TP_TP") (pintype "input"))
    )
    (net (code "53") (name "PP1") (class "Default")
      (node (ref "U1") (pin "119") (pinfunction "PP1_119") (pintype "bidirectional"))
      (node (ref "U6TX") (pin "TP") (pinfunction "TP_TP") (pintype "input"))
    )
    (net (code "54") (name "RBIAS") (class "Default")
      (node (ref "R1") (pin "2") (pinfunction "2_2") (pintype "passive"))
      (node (ref "U1") (pin "59") (pinfunction "RBIAS_59") (pintype "bidirectional"))
    )
    (net (code "55") (name "RST") (class "Default")
      (node (ref "C9") (pin "1") (pinfunction "1_1") (pintype "passive"))
      (node (ref "R6") (pin "1") (pinfunction "1_1") (pintype "passive"))
      (node (ref "R7") (pin "1") (pinfunction "1_1") (pintype "passive"))
      (node (ref "U1") (pin "70") (pinfunction "RST*_70") (pintype "input"))
    )
    (net (code "56") (name "SPKR+") (class "Default")
      (node (ref "SPKR") (pin "2") (pinfunction "2_2") (pintype "passive"))
      (node (ref "U$2") (pin "3") (pinfunction "3_3") (pintype "passive"))
    )
    (net (code "57") (name "SPKR-") (class "Default")
      (node (ref "SPKR") (pin "1") (pinfunction "1_1") (pintype "passive"))
      (node (ref "U$2") (pin "4") (pinfunction "4_4") (pintype "passive"))
    )
    (net (code "58") (name "TCK{slash}SWCLK") (class "Default")
      (node (ref "JTAG") (pin "1") (pinfunction "1_1") (pintype "passive"))
      (node (ref "U1") (pin "100") (pinfunction "PC0_100") (pintype "bidirectional"))
    )
    (net (code "59") (name "TDI") (class "Default")
      (node (ref "JTAG") (pin "3") (pinfunction "3_3") (pintype "passive"))
      (node (ref "U1") (pin "98") (pinfunction "PC2_98") (pintype "bidirectional"))
    )
    (net (code "60") (name "TDO{slash}SWO") (class "Default")
      (node (ref "JTAG") (pin "4") (pinfunction "4_4") (pintype "passive"))
      (node (ref "U1") (pin "97") (pinfunction "PC3_97") (pintype "bidirectional"))
    )
    (net (code "61") (name "TMS{slash}SWDIO") (class "Default")
      (node (ref "JTAG") (pin "2") (pinfunction "2_2") (pintype "passive"))
      (node (ref "U1") (pin "99") (pinfunction "PC1_99") (pintype "bidirectional"))
    )
    (net (code "62") (name "VBAT") (class "Default")
      (node (ref "C5") (pin "1") (pinfunction "1_1") (pintype "passive"))
      (node (ref "R5") (pin "2") (pinfunction "2_2") (pintype "passive"))
      (node (ref "U1") (pin "68") (pinfunction "VBAT_68") (pintype "power_in"))
    )
    (net (code "63") (name "VDDC") (class "Default")
      (node (ref "C6") (pin "1") (pinfunction "1_1") (pintype "passive"))
      (node (ref "C7") (pin "1") (pinfunction "1_1") (pintype "passive"))
      (node (ref "C8") (pin "1") (pinfunction "1_1") (pintype "passive"))
      (node (ref "U1") (pin "115") (pinfunction "VDDC_115") (pintype "power_in"))
      (node (ref "U1") (pin "87") (pinfunction "VDDC_87") (pintype "power_in"))
      (node (ref "VDDC") (pin "TP") (pinfunction "TP_TP") (pintype "input"))
    )
    (net (code "64") (name "VREFA+") (class "Default")
      (node (ref "R2") (pin "1") (pinfunction "1_1") (pintype "passive"))
      (node (ref "U1") (pin "9") (pinfunction "VREFA+_9") (pintype "input"))
      (node (ref "VREFA") (pin "TP") (pinfunction "TP_TP") (pintype "input"))
    )
    (net (code "65") (name "WAKE") (class "Default")
      (node (ref "R4") (pin "2") (pinfunction "2_2") (pintype "passive"))
      (node (ref "U1") (pin "64") (pinfunction "WAKE*_64") (pintype "input"))
      (node (ref "WAKE") (pin "TP") (pinfunction "TP_TP") (pintype "input"))
    )
    (net (code "66") (name "unconnected-(MICRO-USB-Pad2)") (class "Default")
      (node (ref "MICRO-USB") (pin "2") (pinfunction "2_2") (pintype "passive"))
    )
    (net (code "67") (name "unconnected-(MICRO-USB-Pad3)") (class "Default")
      (node (ref "MICRO-USB") (pin "3") (pinfunction "3_3") (pintype "passive"))
    )
    (net (code "68") (name "unconnected-(MICRO-USB-Pad4)") (class "Default")
      (node (ref "MICRO-USB") (pin "4") (pinfunction "4_4") (pintype "passive"))
    )
    (net (code "69") (name "unconnected-(SW1-Pad2)") (class "Default")
      (node (ref "SW1") (pin "2") (pinfunction "2_2") (pintype "output"))
    )
    (net (code "70") (name "unconnected-(SW1-Pad4)") (class "Default")
      (node (ref "SW1") (pin "4") (pinfunction "4_4") (pintype "input"))
    )
    (net (code "71") (name "unconnected-(SW1-Pad5)") (class "Default")
      (node (ref "SW1") (pin "5") (pinfunction "5_5") (pintype "input"))
    )
    (net (code "72") (name "unconnected-(SW1-Pad8)") (class "Default")
      (node (ref "SW1") (pin "8") (pinfunction "8_8") (pintype "input"))
    )
    (net (code "73") (name "unconnected-(U$1-Pad3)") (class "Default")
      (node (ref "U$1") (pin "3") (pinfunction "3_3") (pintype "passive"))
    )
    (net (code "74") (name "unconnected-(U$2-Pad1)") (class "Default")
      (node (ref "U$2") (pin "1") (pinfunction "1_1") (pintype "passive"))
    )
    (net (code "75") (name "unconnected-(U$3-Pad5)") (class "Default")
      (node (ref "U$3") (pin "5") (pinfunction "5_5") (pintype "passive"))
    )
    (net (code "76") (name "unconnected-(U1B-PK0-Pad18)") (class "Default")
      (node (ref "U1") (pin "18") (pinfunction "PK0_18") (pintype "bidirectional"))
    )
    (net (code "77") (name "unconnected-(U1B-PK1-Pad19)") (class "Default")
      (node (ref "U1") (pin "19") (pinfunction "PK1_19") (pintype "bidirectional"))
    )
    (net (code "78") (name "unconnected-(U1B-PK2-Pad20)") (class "Default")
      (node (ref "U1") (pin "20") (pinfunction "PK2_20") (pintype "bidirectional"))
    )
    (net (code "79") (name "unconnected-(U1B-PK3-Pad21)") (class "Default")
      (node (ref "U1") (pin "21") (pinfunction "PK3_21") (pintype "bidirectional"))
    )
    (net (code "80") (name "unconnected-(U1B-PK6-Pad61)") (class "Default")
      (node (ref "U1") (pin "61") (pinfunction "PK6_61") (pintype "bidirectional"))
    )
    (net (code "81") (name "unconnected-(U1B-PK7-Pad60)") (class "Default")
      (node (ref "U1") (pin "60") (pinfunction "PK7_60") (pintype "bidirectional"))
    )
    (net (code "82") (name "unconnected-(U1C-PL0-Pad81)") (class "Default")
      (node (ref "U1") (pin "81") (pinfunction "PL0_81") (pintype "bidirectional"))
    )
    (net (code "83") (name "unconnected-(U1C-PL1-Pad82)") (class "Default")
      (node (ref "U1") (pin "82") (pinfunction "PL1_82") (pintype "bidirectional"))
    )
    (net (code "84") (name "unconnected-(U1C-PL2-Pad83)") (class "Default")
      (node (ref "U1") (pin "83") (pinfunction "PL2_83") (pintype "bidirectional"))
    )
    (net (code "85") (name "unconnected-(U1C-PL3-Pad84)") (class "Default")
      (node (ref "U1") (pin "84") (pinfunction "PL3_84") (pintype "bidirectional"))
    )
    (net (code "86") (name "unconnected-(U1C-PL4-Pad85)") (class "Default")
      (node (ref "U1") (pin "85") (pinfunction "PL4_85") (pintype "bidirectional"))
    )
    (net (code "87") (name "unconnected-(U1C-PL5-Pad86)") (class "Default")
      (node (ref "U1") (pin "86") (pinfunction "PL5_86") (pintype "bidirectional"))
    )
    (net (code "88") (name "unconnected-(U1C-PL6-Pad94)") (class "Default")
      (node (ref "U1") (pin "94") (pinfunction "PL6_94") (pintype "bidirectional"))
    )
    (net (code "89") (name "unconnected-(U1C-PL7-Pad93)") (class "Default")
      (node (ref "U1") (pin "93") (pinfunction "PL7_93") (pintype "bidirectional"))
    )
    (net (code "90") (name "unconnected-(U1D-PM0-Pad78)") (class "Default")
      (node (ref "U1") (pin "78") (pinfunction "PM0_78") (pintype "bidirectional"))
    )
    (net (code "91") (name "unconnected-(U1D-PM1-Pad77)") (class "Default")
      (node (ref "U1") (pin "77") (pinfunction "PM1_77") (pintype "bidirectional"))
    )
    (net (code "92") (name "unconnected-(U1D-PM2-Pad76)") (class "Default")
      (node (ref "U1") (pin "76") (pinfunction "PM2_76") (pintype "bidirectional"))
    )
    (net (code "93") (name "unconnected-(U1D-PM3-Pad75)") (class "Default")
      (node (ref "U1") (pin "75") (pinfunction "PM3_75") (pintype "bidirectional"))
    )
    (net (code "94") (name "unconnected-(U1D-PM4-Pad74)") (class "Default")
      (node (ref "U1") (pin "74") (pinfunction "PM4_74") (pintype "bidirectional"))
    )
    (net (code "95") (name "unconnected-(U1D-PM5-Pad73)") (class "Default")
      (node (ref "U1") (pin "73") (pinfunction "PM5_73") (pintype "bidirectional"))
    )
    (net (code "96") (name "unconnected-(U1D-PM6-Pad72)") (class "Default")
      (node (ref "U1") (pin "72") (pinfunction "PM6_72") (pintype "bidirectional"))
    )
    (net (code "97") (name "unconnected-(U1D-PM7-Pad71)") (class "Default")
      (node (ref "U1") (pin "71") (pinfunction "PM7_71") (pintype "bidirectional"))
    )
    (net (code "98") (name "unconnected-(U1E-PN0-Pad107)") (class "Default")
      (node (ref "U1") (pin "107") (pinfunction "PN0_107") (pintype "bidirectional"))
    )
    (net (code "99") (name "unconnected-(U1E-PN1-Pad108)") (class "Default")
      (node (ref "U1") (pin "108") (pinfunction "PN1_108") (pintype "bidirectional"))
    )
    (net (code "100") (name "unconnected-(U1E-PN2-Pad109)") (class "Default")
      (node (ref "U1") (pin "109") (pinfunction "PN2_109") (pintype "bidirectional"))
    )
    (net (code "101") (name "unconnected-(U1E-PN3-Pad110)") (class "Default")
      (node (ref "U1") (pin "110") (pinfunction "PN3_110") (pintype "bidirectional"))
    )
    (net (code "102") (name "unconnected-(U1E-PN4-Pad111)") (class "Default")
      (node (ref "U1") (pin "111") (pinfunction "PN4_111") (pintype "bidirectional"))
    )
    (net (code "103") (name "unconnected-(U1E-PN5-Pad112)") (class "Default")
      (node (ref "U1") (pin "112") (pinfunction "PN5_112") (pintype "bidirectional"))
    )
    (net (code "104") (name "unconnected-(U1F-PP2-Pad103)") (class "Default")
      (node (ref "U1") (pin "103") (pinfunction "PP2_103") (pintype "bidirectional"))
    )
    (net (code "105") (name "unconnected-(U1F-PP3-Pad104)") (class "Default")
      (node (ref "U1") (pin "104") (pinfunction "PP3_104") (pintype "bidirectional"))
    )
    (net (code "106") (name "unconnected-(U1F-PP4-Pad105)") (class "Default")
      (node (ref "U1") (pin "105") (pinfunction "PP4_105") (pintype "bidirectional"))
    )
    (net (code "107") (name "unconnected-(U1F-PP5-Pad106)") (class "Default")
      (node (ref "U1") (pin "106") (pinfunction "PP5_106") (pintype "bidirectional"))
    )
    (net (code "108") (name "unconnected-(U1G-PQ0-Pad5)") (class "Default")
      (node (ref "U1") (pin "5") (pinfunction "PQ0_5") (pintype "bidirectional"))
    )
    (net (code "109") (name "unconnected-(U1G-PQ1-Pad6)") (class "Default")
      (node (ref "U1") (pin "6") (pinfunction "PQ1_6") (pintype "bidirectional"))
    )
    (net (code "110") (name "unconnected-(U1G-PQ2-Pad11)") (class "Default")
      (node (ref "U1") (pin "11") (pinfunction "PQ2_11") (pintype "bidirectional"))
    )
    (net (code "111") (name "unconnected-(U1G-PQ3-Pad27)") (class "Default")
      (node (ref "U1") (pin "27") (pinfunction "PQ3_27") (pintype "bidirectional"))
    )
    (net (code "112") (name "unconnected-(U1G-PQ4-Pad102)") (class "Default")
      (node (ref "U1") (pin "102") (pinfunction "PQ4_102") (pintype "bidirectional"))
    )
    (net (code "113") (name "unconnected-(U1I-EN0RXIN-Pad53)") (class "Default")
      (node (ref "U1") (pin "53") (pinfunction "EN0RXIN_53") (pintype "bidirectional"))
    )
    (net (code "114") (name "unconnected-(U1I-EN0RXIP-Pad54)") (class "Default")
      (node (ref "U1") (pin "54") (pinfunction "EN0RXIP_54") (pintype "bidirectional"))
    )
    (net (code "115") (name "unconnected-(U1I-EN0TXON-Pad56)") (class "Default")
      (node (ref "U1") (pin "56") (pinfunction "EN0TXON_56") (pintype "bidirectional"))
    )
    (net (code "116") (name "unconnected-(U1I-EN0TXOP-Pad57)") (class "Default")
      (node (ref "U1") (pin "57") (pinfunction "EN0TXOP_57") (pintype "bidirectional"))
    )
    (net (code "117") (name "unconnected-(U1I-XOSC0-Pad66)") (class "Default")
      (node (ref "U1") (pin "66") (pinfunction "XOSC0_66") (pintype "bidirectional"))
    )
    (net (code "118") (name "unconnected-(U1I-XOSC1-Pad67)") (class "Default")
      (node (ref "U1") (pin "67") (pinfunction "XOSC1_67") (pintype "bidirectional"))
    )
    (net (code "119") (name "unconnected-(U1K-PB0-Pad95)") (class "Default")
      (node (ref "U1") (pin "95") (pinfunction "PB0_95") (pintype "bidirectional"))
    )
    (net (code "120") (name "unconnected-(U1K-PB1-Pad96)") (class "Default")
      (node (ref "U1") (pin "96") (pinfunction "PB1_96") (pintype "bidirectional"))
    )
    (net (code "121") (name "unconnected-(U1K-PB2-Pad91)") (class "Default")
      (node (ref "U1") (pin "91") (pinfunction "PB2_91") (pintype "bidirectional"))
    )
    (net (code "122") (name "unconnected-(U1K-PB3-Pad92)") (class "Default")
      (node (ref "U1") (pin "92") (pinfunction "PB3_92") (pintype "bidirectional"))
    )
    (net (code "123") (name "unconnected-(U1L-PC4-Pad25)") (class "Default")
      (node (ref "U1") (pin "25") (pinfunction "PC4_25") (pintype "bidirectional"))
    )
    (net (code "124") (name "unconnected-(U1L-PC5-Pad24)") (class "Default")
      (node (ref "U1") (pin "24") (pinfunction "PC5_24") (pintype "bidirectional"))
    )
    (net (code "125") (name "unconnected-(U1M-PD6-Pad127)") (class "Default")
      (node (ref "U1") (pin "127") (pinfunction "PD6_127") (pintype "bidirectional"))
    )
    (net (code "126") (name "unconnected-(U1O-PF0-Pad42)") (class "Default")
      (node (ref "U1") (pin "42") (pinfunction "PF0_42") (pintype "bidirectional"))
    )
    (net (code "127") (name "unconnected-(U1O-PF1-Pad43)") (class "Default")
      (node (ref "U1") (pin "43") (pinfunction "PF1_43") (pintype "bidirectional"))
    )
    (net (code "128") (name "unconnected-(U1O-PF2-Pad44)") (class "Default")
      (node (ref "U1") (pin "44") (pinfunction "PF2_44") (pintype "bidirectional"))
    )
    (net (code "129") (name "unconnected-(U1O-PF3-Pad45)") (class "Default")
      (node (ref "U1") (pin "45") (pinfunction "PF3_45") (pintype "bidirectional"))
    )
    (net (code "130") (name "unconnected-(U1O-PF4-Pad46)") (class "Default")
      (node (ref "U1") (pin "46") (pinfunction "PF4_46") (pintype "bidirectional"))
    )
    (net (code "131") (name "unconnected-(U1P-PG0-Pad49)") (class "Default")
      (node (ref "U1") (pin "49") (pinfunction "PG0_49") (pintype "bidirectional"))
    )
    (net (code "132") (name "unconnected-(U1P-PG1-Pad50)") (class "Default")
      (node (ref "U1") (pin "50") (pinfunction "PG1_50") (pintype "bidirectional"))
    )
    (net (code "133") (name "unconnected-(U1Q-PH0-Pad29)") (class "Default")
      (node (ref "U1") (pin "29") (pinfunction "PH0_29") (pintype "bidirectional"))
    )
    (net (code "134") (name "unconnected-(U1Q-PH1-Pad30)") (class "Default")
      (node (ref "U1") (pin "30") (pinfunction "PH1_30") (pintype "bidirectional"))
    )
    (net (code "135") (name "unconnected-(U1Q-PH2-Pad31)") (class "Default")
      (node (ref "U1") (pin "31") (pinfunction "PH2_31") (pintype "bidirectional"))
    )
    (net (code "136") (name "unconnected-(U1Q-PH3-Pad32)") (class "Default")
      (node (ref "U1") (pin "32") (pinfunction "PH3_32") (pintype "bidirectional"))
    )
    (net (code "137") (name "unconnected-(U1R-PJ0-Pad116)") (class "Default")
      (node (ref "U1") (pin "116") (pinfunction "PJ0_116") (pintype "bidirectional"))
    )
    (net (code "138") (name "unconnected-(U1R-PJ1-Pad117)") (class "Default")
      (node (ref "U1") (pin "117") (pinfunction "PJ1_117") (pintype "bidirectional"))
    )
  )
)
